# ALIMENTACION.net
KiCad netlist of a schematic drawn in Altium Designer
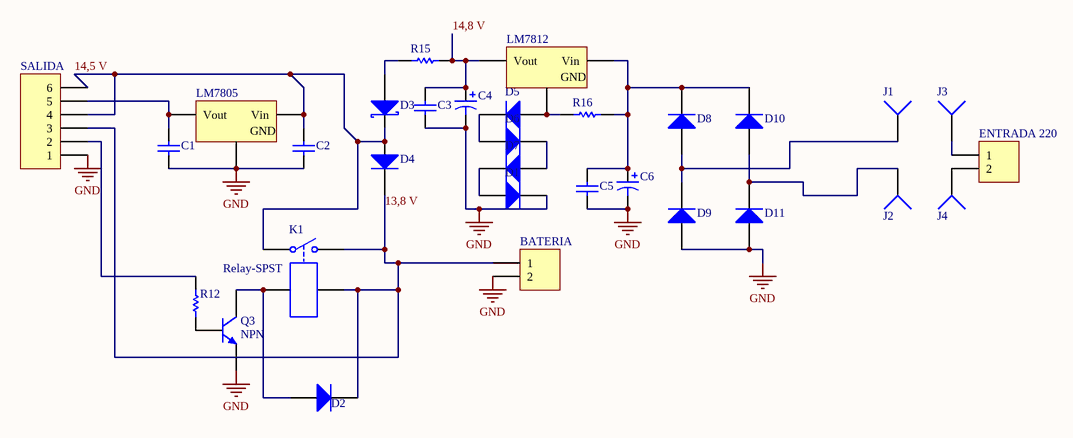
[diagram p0: ALIMENTACION.SchDoc]

(export (version "E")
  (design (tool "Eeschema 10.0.6"))
  (components
    (comp (ref "BATERIA")
      (value "Header 2")
      (footprint "Bornera 2 pin")
      (description "Header, 2-Pin")
      (fields (field (name "PUBLISHER") "Altium Limited"))
      (libsource (lib "Miscellaneous Connectors") (part "Header 2"))
    )
    (comp (ref "C1")
      (value "Cap")
      (footprint "C Disc 8x2.5-5.0")
      (description "Capacitor")
      (fields (field (name "PUBLISHER") "Altium Limited"))
      (libsource (lib "Miscellaneous Devices") (part "Cap"))
    )
    (comp (ref "C2")
      (value "Cap")
      (footprint "C Disc 8x2.5-5.0")
      (description "Capacitor")
      (fields (field (name "PUBLISHER") "Altium Limited"))
      (libsource (lib "Miscellaneous Devices") (part "Cap"))
    )
    (comp (ref "C3")
      (value "Cap")
      (footprint "C Disc 8x2.5-5.0")
      (description "Capacitor")
      (fields (field (name "PUBLISHER") "Altium Limited"))
      (libsource (lib "Miscellaneous Devices") (part "Cap"))
    )
    (comp (ref "C4")
      (value "Cap Pol1")
      (footprint "RB7.6-15")
      (description "Polarized Capacitor (Radial)")
      (fields (field (name "PUBLISHER") "Altium Limited"))
      (libsource (lib "Miscellaneous Devices") (part "Cap Pol1"))
    )
    (comp (ref "C5")
      (value "Cap")
      (footprint "C Disc 8x2.5-5.0")
      (description "Capacitor")
      (fields (field (name "PUBLISHER") "Altium Limited"))
      (libsource (lib "Miscellaneous Devices") (part "Cap"))
    )
    (comp (ref "C6")
      (value "Cap Pol1")
      (footprint "RB7.6-15")
      (description "Polarized Capacitor (Radial)")
      (fields (field (name "PUBLISHER") "Altium Limited"))
      (libsource (lib "Miscellaneous Devices") (part "Cap Pol1"))
    )
    (comp (ref "D1")
      (value "Diode 1N914")
      (footprint "DO-35 Glass")
      (description "High Conductance Fast Diode")
      (fields (field (name "PUBLISHER") "Altium Limited"))
      (libsource (lib "Miscellaneous Devices") (part "Diode 1N914"))
    )
    (comp (ref "D2")
      (value "Diode 1N914")
      (footprint "DO-35 Glass")
      (description "High Conductance Fast Diode")
      (fields (field (name "PUBLISHER") "Altium Limited"))
      (libsource (lib "Miscellaneous Devices") (part "Diode 1N914"))
    )
    (comp (ref "D3")
      (value "D Schottky")
      (footprint "DO-35 Glass")
      (description "Schottky Diode")
      (fields (field (name "PUBLISHER") "Altium Limited"))
      (libsource (lib "Miscellaneous Devices") (part "D Schottky"))
    )
    (comp (ref "D4")
      (value "Diode 1N914")
      (footprint "DO-35 Glass")
      (description "High Conductance Fast Diode")
      (fields (field (name "PUBLISHER") "Altium Limited"))
      (libsource (lib "Miscellaneous Devices") (part "Diode 1N914"))
    )
    (comp (ref "D5")
      (value "Diode 1N914")
      (footprint "DO-35 Glass")
      (description "High Conductance Fast Diode")
      (fields (field (name "PUBLISHER") "Altium Limited"))
      (libsource (lib "Miscellaneous Devices") (part "Diode 1N914"))
    )
    (comp (ref "D6")
      (value "Diode 1N914")
      (footprint "DO-35 Glass")
      (description "High Conductance Fast Diode")
      (fields (field (name "PUBLISHER") "Altium Limited"))
      (libsource (lib "Miscellaneous Devices") (part "Diode 1N914"))
    )
    (comp (ref "D7")
      (value "Diode 1N914")
      (footprint "DO-35 Glass")
      (description "High Conductance Fast Diode")
      (fields (field (name "PUBLISHER") "Altium Limited"))
      (libsource (lib "Miscellaneous Devices") (part "Diode 1N914"))
    )
    (comp (ref "D8")
      (value "Diode 1N914")
      (footprint "DO-35 Glass")
      (description "High Conductance Fast Diode")
      (fields (field (name "PUBLISHER") "Altium Limited"))
      (libsource (lib "Miscellaneous Devices") (part "Diode 1N914"))
    )
    (comp (ref "D9")
      (value "Diode 1N914")
      (footprint "DO-35 Glass")
      (description "High Conductance Fast Diode")
      (fields (field (name "PUBLISHER") "Altium Limited"))
      (libsource (lib "Miscellaneous Devices") (part "Diode 1N914"))
    )
    (comp (ref "D10")
      (value "Diode 1N914")
      (footprint "DO-35 Glass")
      (description "High Conductance Fast Diode")
      (fields (field (name "PUBLISHER") "Altium Limited"))
      (libsource (lib "Miscellaneous Devices") (part "Diode 1N914"))
    )
    (comp (ref "D11")
      (value "Diode 1N914")
      (footprint "DO-35 Glass")
      (description "High Conductance Fast Diode")
      (fields (field (name "PUBLISHER") "Altium Limited"))
      (libsource (lib "Miscellaneous Devices") (part "Diode 1N914"))
    )
    (comp (ref "ENTRADA 220")
      (value "220V")
      (footprint "Bornera 2 pin")
      (description "Header, 2-Pin")
      (fields (field (name "PUBLISHER") "Altium Limited"))
      (libsource (lib "Miscellaneous Connectors") (part "Header 2"))
    )
    (comp (ref "J1")
      (value "Socket")
      (footprint "PIN1")
      (fields (field (name "PUBLISHER") "Altium Limited"))
      (libsource (lib "Miscellaneous Connectors") (part "Socket"))
    )
    (comp (ref "J2")
      (value "Socket")
      (footprint "PIN1")
      (fields (field (name "PUBLISHER") "Altium Limited"))
      (libsource (lib "Miscellaneous Connectors") (part "Socket"))
    )
    (comp (ref "J3")
      (value "Socket")
      (footprint "PIN1")
      (fields (field (name "PUBLISHER") "Altium Limited"))
      (libsource (lib "Miscellaneous Connectors") (part "Socket"))
    )
    (comp (ref "J4")
      (value "Socket")
      (footprint "PIN1")
      (fields (field (name "PUBLISHER") "Altium Limited"))
      (libsource (lib "Miscellaneous Connectors") (part "Socket"))
    )
    (comp (ref "K1")
      (value "Relay-SPST")
      (footprint "MODULE4")
      (description "Single-Pole Single-Throw Relay")
      (fields (field (name "PUBLISHER") "Altium Limited"))
      (libsource (lib "Miscellaneous Devices") (part "Relay-SPST"))
    )
    (comp (ref "LM7805")
      (value "Volt Reg")
      (footprint "TO-220AB")
      (description "Voltage Regulator")
      (fields (field (name "PUBLISHER") "Altium Limited"))
      (libsource (lib "Miscellaneous Devices") (part "Volt Reg"))
    )
    (comp (ref "LM7812")
      (value "Volt Reg")
      (footprint "TO-220AB")
      (description "Voltage Regulator")
      (fields (field (name "PUBLISHER") "Altium Limited"))
      (libsource (lib "Miscellaneous Devices") (part "Volt Reg"))
    )
    (comp (ref "Q3")
      (value "NPN")
      (footprint "TO-226-AA")
      (description "NPN Bipolar Transistor")
      (fields (field (name "PUBLISHER") "Altium Limited"))
      (libsource (lib "Miscellaneous Devices") (part "NPN"))
    )
    (comp (ref "R12")
      (value "Res1")
      (footprint "R Axial 0.4")
      (description "Resistor")
      (fields (field (name "PUBLISHER") "Altium Limited"))
      (libsource (lib "Miscellaneous Devices") (part "Res1"))
    )
    (comp (ref "R15")
      (value "Res1")
      (footprint "AXIAL-0.3")
      (description "Resistor")
      (fields (field (name "PUBLISHER") "Altium Limited"))
      (libsource (lib "Miscellaneous Devices") (part "Res1"))
    )
    (comp (ref "R16")
      (value "Res1")
      (footprint "AXIAL-0.3")
      (description "Resistor")
      (fields (field (name "PUBLISHER") "Altium Limited"))
      (libsource (lib "Miscellaneous Devices") (part "Res1"))
    )
    (comp (ref "SALIDA")
      (value "Header 6")
      (footprint "BORNERA 6 PIN")
      (description "Header, 6-Pin")
      (fields (field (name "PUBLISHER") "Altium Limited"))
      (libsource (lib "Miscellaneous Connectors") (part "Header 6"))
    )
  )
  (nets
    (net (code "1") (name "/13,8 V") (class "Default")
      (node (ref "BATERIA") (pin "1") (pinfunction "1_1") (pintype "passive"))
      (node (ref "D2") (pin "2") (pinfunction "K_2") (pintype "passive"))
      (node (ref "D4") (pin "2") (pinfunction "K_2") (pintype "passive"))
      (node (ref "K1") (pin "2") (pinfunction "2_2") (pintype "passive"))
      (node (ref "K1") (pin "4") (pinfunction "4_4") (pintype "passive"))
      (node (ref "SALIDA") (pin "3") (pinfunction "3_3") (pintype "passive"))
    )
    (net (code "2") (name "/14,5 V") (class "Default")
      (node (ref "C2") (pin "2") (pinfunction "2_2") (pintype "passive"))
      (node (ref "D3") (pin "2") (pinfunction "K_2") (pintype "passive"))
      (node (ref "D4") (pin "1") (pinfunction "A_1") (pintype "passive"))
      (node (ref "K1") (pin "1") (pinfunction "1_1") (pintype "passive"))
      (node (ref "LM7805") (pin "1") (pinfunction "Vin_1") (pintype "passive"))
      (node (ref "SALIDA") (pin "4") (pinfunction "4_4") (pintype "passive"))
      (node (ref "SALIDA") (pin "6") (pinfunction "6_6") (pintype "passive"))
    )
    (net (code "3") (name "/14,8 V") (class "Default")
      (node (ref "C3") (pin "2") (pinfunction "2_2") (pintype "passive"))
      (node (ref "C4") (pin "1") (pinfunction "1_1") (pintype "passive"))
      (node (ref "LM7812") (pin "3") (pinfunction "Vout_3") (pintype "passive"))
      (node (ref "R15") (pin "2") (pinfunction "2_2") (pintype "passive"))
    )
    (net (code "4") (name "GND") (class "Default")
      (node (ref "BATERIA") (pin "2") (pinfunction "2_2") (pintype "passive"))
      (node (ref "C1") (pin "1") (pinfunction "1_1") (pintype "passive"))
      (node (ref "C2") (pin "1") (pinfunction "1_1") (pintype "passive"))
      (node (ref "C3") (pin "1") (pinfunction "1_1") (pintype "passive"))
      (node (ref "C4") (pin "2") (pinfunction "2_2") (pintype "passive"))
      (node (ref "C5") (pin "1") (pinfunction "1_1") (pintype "passive"))
      (node (ref "C6") (pin "2") (pinfunction "2_2") (pintype "passive"))
      (node (ref "D1") (pin "2") (pinfunction "K_2") (pintype "passive"))
      (node (ref "D11") (pin "1") (pinfunction "A_1") (pintype "passive"))
      (node (ref "D9") (pin "1") (pinfunction "A_1") (pintype "passive"))
      (node (ref "LM7805") (pin "2") (pinfunction "GND_2") (pintype "passive"))
      (node (ref "Q3") (pin "3") (pinfunction "E_3") (pintype "passive"))
      (node (ref "SALIDA") (pin "1") (pinfunction "1_1") (pintype "passive"))
    )
    (net (code "5") (name "Net-(D1-A)") (class "Default")
      (node (ref "D1") (pin "1") (pinfunction "A_1") (pintype "passive"))
      (node (ref "D7") (pin "2") (pinfunction "K_2") (pintype "passive"))
    )
    (net (code "6") (name "Net-(D2-A)") (class "Default")
      (node (ref "D2") (pin "1") (pinfunction "A_1") (pintype "passive"))
      (node (ref "K1") (pin "3") (pinfunction "3_3") (pintype "passive"))
      (node (ref "Q3") (pin "1") (pinfunction "C_1") (pintype "passive"))
    )
    (net (code "7") (name "Net-(D3-A)") (class "Default")
      (node (ref "D3") (pin "1") (pinfunction "A_1") (pintype "passive"))
      (node (ref "R15") (pin "1") (pinfunction "1_1") (pintype "passive"))
    )
    (net (code "8") (name "Net-(D5-A)") (class "Default")
      (node (ref "D5") (pin "1") (pinfunction "A_1") (pintype "passive"))
      (node (ref "LM7812") (pin "2") (pinfunction "GND_2") (pintype "passive"))
      (node (ref "R16") (pin "1") (pinfunction "1_1") (pintype "passive"))
    )
    (net (code "9") (name "Net-(D5-K)") (class "Default")
      (node (ref "D5") (pin "2") (pinfunction "K_2") (pintype "passive"))
      (node (ref "D6") (pin "1") (pinfunction "A_1") (pintype "passive"))
    )
    (net (code "10") (name "Net-(D6-K)") (class "Default")
      (node (ref "D6") (pin "2") (pinfunction "K_2") (pintype "passive"))
      (node (ref "D7") (pin "1") (pinfunction "A_1") (pintype "passive"))
    )
    (net (code "11") (name "Net-(D8-A)") (class "Default")
      (node (ref "D8") (pin "1") (pinfunction "A_1") (pintype "passive"))
      (node (ref "D9") (pin "2") (pinfunction "K_2") (pintype "passive"))
      (node (ref "J1") (pin "1") (pinfunction "1_1") (pintype "passive"))
    )
    (net (code "12") (name "Net-(D10-A)") (class "Default")
      (node (ref "D10") (pin "1") (pinfunction "A_1") (pintype "passive"))
      (node (ref "D11") (pin "2") (pinfunction "K_2") (pintype "passive"))
      (node (ref "J2") (pin "1") (pinfunction "1_1") (pintype "passive"))
    )
    (net (code "13") (name "Net-(D10-K)") (class "Default")
      (node (ref "C5") (pin "2") (pinfunction "2_2") (pintype "passive"))
      (node (ref "C6") (pin "1") (pinfunction "1_1") (pintype "passive"))
      (node (ref "D10") (pin "2") (pinfunction "K_2") (pintype "passive"))
      (node (ref "D8") (pin "2") (pinfunction "K_2") (pintype "passive"))
      (node (ref "LM7812") (pin "1") (pinfunction "Vin_1") (pintype "passive"))
      (node (ref "R16") (pin "2") (pinfunction "2_2") (pintype "passive"))
    )
    (net (code "14") (name "Net-(ENTRADA 220-Pad1)") (class "Default")
      (node (ref "ENTRADA 220") (pin "1") (pinfunction "1_1") (pintype "passive"))
      (node (ref "J3") (pin "1") (pinfunction "1_1") (pintype "passive"))
    )
    (net (code "15") (name "Net-(ENTRADA 220-Pad2)") (class "Default")
      (node (ref "ENTRADA 220") (pin "2") (pinfunction "2_2") (pintype "passive"))
      (node (ref "J4") (pin "1") (pinfunction "1_1") (pintype "passive"))
    )
    (net (code "16") (name "Net-(LM7805-Vout)") (class "Default")
      (node (ref "C1") (pin "2") (pinfunction "2_2") (pintype "passive"))
      (node (ref "LM7805") (pin "3") (pinfunction "Vout_3") (pintype "passive"))
      (node (ref "SALIDA") (pin "5") (pinfunction "5_5") (pintype "passive"))
    )
    (net (code "17") (name "Net-(Q3-B)") (class "Default")
      (node (ref "Q3") (pin "2") (pinfunction "B_2") (pintype "passive"))
      (node (ref "R12") (pin "2") (pinfunction "2_2") (pintype "passive"))
    )
    (net (code "18") (name "Net-(R12-Pad1)") (class "Default")
      (node (ref "R12") (pin "1") (pinfunction "1_1") (pintype "passive"))
      (node (ref "SALIDA") (pin "2") (pinfunction "2_2") (pintype "passive"))
    )
  )
)
